# Main_Schematic.net
KiCad netlist of a schematic drawn in Altium Designer
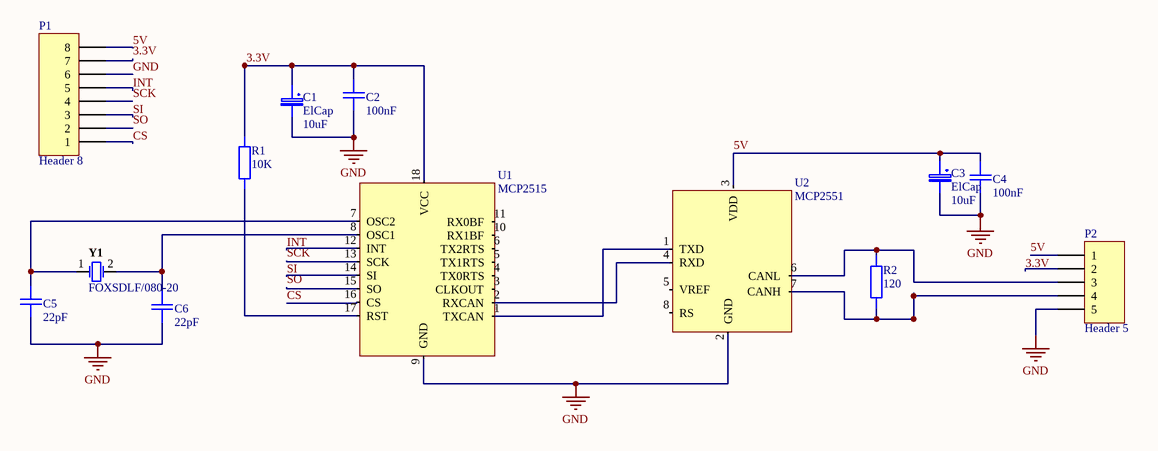
[diagram p0: Main Schematic.SchDoc]

(export (version "E")
  (design (tool "Eeschema 10.0.6"))
  (components
    (comp (ref "C1")
      (value "ElCap")
      (footprint "CAPAE4343X55M")
      (fields
        (field (name "TOLERANCE") "20%")
        (field (name "VOLTAGE") "16V")
        (field (name "ALTIUM_VALUE") "10uF")
      )
      (libsource (lib "Finished") (part "ElCap"))
    )
    (comp (ref "C2")
      (value "100nF")
      (footprint "CAP0805")
      (fields
        (field (name "VOLTAGE") "16V")
        (field (name "TOLERANCE") "10%")
        (field (name "Comment") "Capacitor")
      )
      (libsource (lib "Orbit") (part "Capacitor"))
    )
    (comp (ref "C3")
      (value "ElCap")
      (footprint "CAPAE4343X55M")
      (fields
        (field (name "TOLERANCE") "20%")
        (field (name "VOLTAGE") "16V")
        (field (name "ALTIUM_VALUE") "10uF")
      )
      (libsource (lib "Finished") (part "ElCap"))
    )
    (comp (ref "C4")
      (value "100nF")
      (footprint "CAP0805")
      (fields
        (field (name "VOLTAGE") "16V")
        (field (name "TOLERANCE") "10%")
        (field (name "Comment") "Capacitor")
      )
      (libsource (lib "Orbit") (part "Capacitor"))
    )
    (comp (ref "C5")
      (value "22pF")
      (footprint "CAP0805")
      (fields
        (field (name "VOLTAGE") "16V")
        (field (name "TOLERANCE") "10%")
        (field (name "Comment") "Capacitor")
      )
      (libsource (lib "Orbit") (part "Capacitor"))
    )
    (comp (ref "C6")
      (value "22pF")
      (footprint "CAP0805")
      (fields
        (field (name "VOLTAGE") "16V")
        (field (name "TOLERANCE") "10%")
        (field (name "Comment") "Capacitor")
      )
      (libsource (lib "Orbit") (part "Capacitor"))
    )
    (comp (ref "P1")
      (value "Header 8")
      (footprint "HDR1X8")
      (description "Header, 8-Pin")
      (fields (field (name "PUBLISHER") "Altium Limited"))
      (libsource (lib "Miscellaneous Connectors") (part "Header 8"))
    )
    (comp (ref "P2")
      (value "Header 5")
      (footprint "HDR1X5")
      (description "Header, 5-Pin")
      (fields (field (name "PUBLISHER") "Altium Limited"))
      (libsource (lib "Miscellaneous Connectors") (part "Header 5"))
    )
    (comp (ref "R1")
      (value "10K")
      (footprint "6-0805_L")
      (fields (field (name "TOLERANCE") "1%") (field (name "Comment") "Resistor"))
      (libsource (lib "Orbit") (part "Resistor"))
    )
    (comp (ref "R2")
      (value "120")
      (footprint "6-0805_L")
      (fields (field (name "TOLERANCE") "1%") (field (name "Comment") "Resistor"))
      (libsource (lib "Orbit") (part "Resistor"))
    )
    (comp (ref "U1")
      (value "MCP2515")
      (footprint "TSSOP 20-lead 4.4mm")
      (libsource (lib "Orbit") (part "MCP2515"))
    )
    (comp (ref "U2")
      (value "MCP2551")
      (footprint "SOIC 8-LEAD SN")
      (libsource (lib "Orbit") (part "MCP2551"))
    )
    (comp (ref "Y1")
      (value "FOXSDLF/080-20")
      (footprint "FOX-HC49SDLF_V")
      (description "Resistance Weld Crystal, 8 MHz, +/- 30 ppm, -20 to 70 degC, 2-Pin SMD, RoHS, Tape and Reel")
      (fields (field (name "MANUFACTURER") "FOX Electronics") (field (name "TOLERANCE") "50ppm"))
      (libsource (lib "Altium Content Vault") (part "XTAL-1-2-2"))
    )
  )
  (nets
    (net (code "1") (name "/3.3V") (class "Default")
      (node (ref "C1") (pin "1") (pinfunction "1_1") (pintype "passive"))
      (node (ref "C2") (pin "1") (pinfunction "1_1") (pintype "passive"))
      (node (ref "P1") (pin "7") (pinfunction "7_7") (pintype "passive"))
      (node (ref "P2") (pin "2") (pinfunction "2_2") (pintype "passive"))
      (node (ref "R1") (pin "2") (pinfunction "2_2") (pintype "passive"))
      (node (ref "U1") (pin "18") (pinfunction "VCC_18") (pintype "power_in"))
    )
    (net (code "2") (name "/5V") (class "Default")
      (node (ref "C3") (pin "1") (pinfunction "1_1") (pintype "passive"))
      (node (ref "C4") (pin "1") (pinfunction "1_1") (pintype "passive"))
      (node (ref "P1") (pin "8") (pinfunction "8_8") (pintype "passive"))
      (node (ref "P2") (pin "1") (pinfunction "1_1") (pintype "passive"))
      (node (ref "U2") (pin "3") (pinfunction "VDD_3") (pintype "power_in"))
    )
    (net (code "3") (name "/CS") (class "Default")
      (node (ref "P1") (pin "1") (pinfunction "1_1") (pintype "passive"))
      (node (ref "U1") (pin "16") (pinfunction "CS_16") (pintype "passive"))
    )
    (net (code "4") (name "/INT") (class "Default")
      (node (ref "P1") (pin "5") (pinfunction "5_5") (pintype "passive"))
      (node (ref "U1") (pin "12") (pinfunction "INT_12") (pintype "passive"))
    )
    (net (code "5") (name "/SCK") (class "Default")
      (node (ref "P1") (pin "4") (pinfunction "4_4") (pintype "passive"))
      (node (ref "U1") (pin "13") (pinfunction "SCK_13") (pintype "input"))
    )
    (net (code "6") (name "/SI") (class "Default")
      (node (ref "P1") (pin "3") (pinfunction "3_3") (pintype "passive"))
      (node (ref "U1") (pin "14") (pinfunction "SI_14") (pintype "input"))
    )
    (net (code "7") (name "/SO") (class "Default")
      (node (ref "P1") (pin "2") (pinfunction "2_2") (pintype "passive"))
      (node (ref "U1") (pin "15") (pinfunction "SO_15") (pintype "output"))
    )
    (net (code "8") (name "GND") (class "Default")
      (node (ref "C1") (pin "2") (pinfunction "2_2") (pintype "passive"))
      (node (ref "C2") (pin "2") (pinfunction "2_2") (pintype "passive"))
      (node (ref "C3") (pin "2") (pinfunction "2_2") (pintype "passive"))
      (node (ref "C4") (pin "2") (pinfunction "2_2") (pintype "passive"))
      (node (ref "C5") (pin "2") (pinfunction "2_2") (pintype "passive"))
      (node (ref "C6") (pin "2") (pinfunction "2_2") (pintype "passive"))
      (node (ref "P1") (pin "6") (pinfunction "6_6") (pintype "passive"))
      (node (ref "P2") (pin "5") (pinfunction "5_5") (pintype "passive"))
      (node (ref "U1") (pin "9") (pinfunction "GND_9") (pintype "power_in"))
      (node (ref "U2") (pin "2") (pinfunction "GND_2") (pintype "power_in"))
    )
    (net (code "9") (name "Net-(U1-OSC1)") (class "Default")
      (node (ref "C6") (pin "1") (pinfunction "1_1") (pintype "passive"))
      (node (ref "U1") (pin "8") (pinfunction "OSC1_8") (pintype "passive"))
      (node (ref "Y1") (pin "2") (pinfunction "2_2") (pintype "passive"))
    )
    (net (code "10") (name "Net-(U1-OSC2)") (class "Default")
      (node (ref "C5") (pin "1") (pinfunction "1_1") (pintype "passive"))
      (node (ref "U1") (pin "7") (pinfunction "OSC2_7") (pintype "passive"))
      (node (ref "Y1") (pin "1") (pinfunction "1_1") (pintype "passive"))
    )
    (net (code "11") (name "Net-(U1-RST)") (class "Default")
      (node (ref "R1") (pin "1") (pinfunction "1_1") (pintype "passive"))
      (node (ref "U1") (pin "17") (pinfunction "RST_17") (pintype "passive"))
    )
    (net (code "12") (name "Net-(U1-RXCAN)") (class "Default")
      (node (ref "U1") (pin "2") (pinfunction "RXCAN_2") (pintype "passive"))
      (node (ref "U2") (pin "4") (pinfunction "RXD_4") (pintype "input"))
    )
    (net (code "13") (name "Net-(U1-TXCAN)") (class "Default")
      (node (ref "U1") (pin "1") (pinfunction "TXCAN_1") (pintype "passive"))
      (node (ref "U2") (pin "1") (pinfunction "TXD_1") (pintype "output"))
    )
    (net (code "14") (name "Net-(U2-CANH)") (class "Default")
      (node (ref "P2") (pin "4") (pinfunction "4_4") (pintype "passive"))
      (node (ref "R2") (pin "1") (pinfunction "1_1") (pintype "passive"))
      (node (ref "U2") (pin "7") (pinfunction "CANH_7") (pintype "bidirectional"))
    )
    (net (code "15") (name "Net-(U2-CANL)") (class "Default")
      (node (ref "P2") (pin "3") (pinfunction "3_3") (pintype "passive"))
      (node (ref "R2") (pin "2") (pinfunction "2_2") (pintype "passive"))
      (node (ref "U2") (pin "6") (pinfunction "CANL_6") (pintype "bidirectional"))
    )
    (net (code "16") (name "unconnected-(U1-CLKOUT-Pad3)") (class "Default")
      (node (ref "U1") (pin "3") (pinfunction "CLKOUT_3") (pintype "passive"))
    )
    (net (code "17") (name "unconnected-(U1-RX0BF-Pad11)") (class "Default")
      (node (ref "U1") (pin "11") (pinfunction "RX0BF_11") (pintype "passive"))
    )
    (net (code "18") (name "unconnected-(U1-RX1BF-Pad10)") (class "Default")
      (node (ref "U1") (pin "10") (pinfunction "RX1BF_10") (pintype "passive"))
    )
    (net (code "19") (name "unconnected-(U1-TX0RTS-Pad4)") (class "Default")
      (node (ref "U1") (pin "4") (pinfunction "TX0RTS_4") (pintype "passive"))
    )
    (net (code "20") (name "unconnected-(U1-TX1RTS-Pad5)") (class "Default")
      (node (ref "U1") (pin "5") (pinfunction "TX1RTS_5") (pintype "passive"))
    )
    (net (code "21") (name "unconnected-(U1-TX2RTS-Pad6)") (class "Default")
      (node (ref "U1") (pin "6") (pinfunction "TX2RTS_6") (pintype "passive"))
    )
    (net (code "22") (name "unconnected-(U2-RS-Pad8)") (class "Default")
      (node (ref "U2") (pin "8") (pinfunction "RS_8") (pintype "input"))
    )
    (net (code "23") (name "unconnected-(U2-VREF-Pad5)") (class "Default")
      (node (ref "U2") (pin "5") (pinfunction "VREF_5") (pintype "input"))
    )
  )
)
